# esquematico.net
KiCad netlist of a schematic drawn in Altium Designer
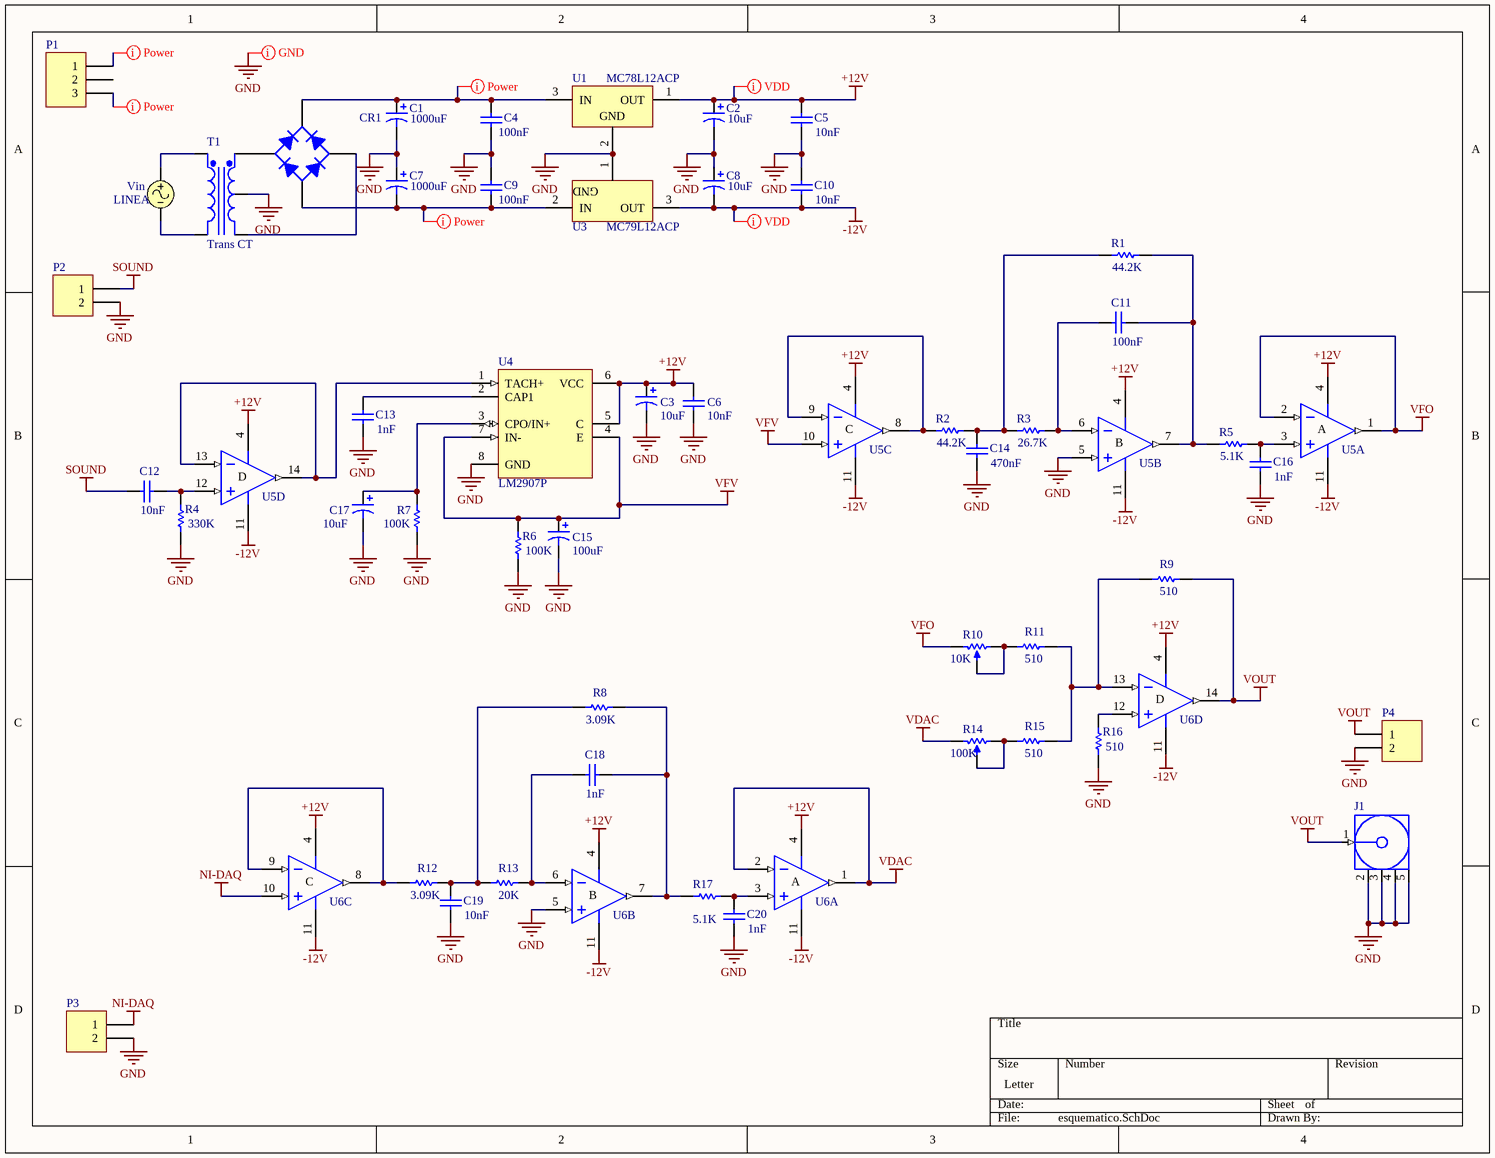
[diagram p0: esquematico.SchDoc]

(export (version "E")
  (design (tool "Eeschema 10.0.6"))
  (components
    (comp (ref "C1")
      (value "1000uF")
      (footprint "CAPPR5-10x20/H1.1")
      (description "Polarized Capacitor (Radial)")
      (fields (field (name "Comment") "Cap Pol1") (field (name "PUBLISHER") "Altium Limited"))
      (libsource (lib "Miscellaneous Devices") (part "Cap Pol1"))
    )
    (comp (ref "C2")
      (value "10uF")
      (footprint "CAPPR2-5x11")
      (description "Polarized Capacitor (Radial)")
      (fields (field (name "Comment") "Cap Pol1") (field (name "PUBLISHER") "Altium Limited"))
      (libsource (lib "Miscellaneous Devices") (part "Cap Pol1"))
    )
    (comp (ref "C3")
      (value "10uF")
      (footprint "CAPPR2-5x11")
      (description "Polarized Capacitor (Radial)")
      (fields (field (name "Comment") "Cap Pol1") (field (name "PUBLISHER") "Altium Limited"))
      (libsource (lib "Miscellaneous Devices") (part "Cap Pol1"))
    )
    (comp (ref "C4")
      (value "100nF")
      (footprint "CAPR2.54-4x2.5")
      (description "Capacitor")
      (fields (field (name "Comment") "Cap") (field (name "PUBLISHER") "Altium Limited"))
      (libsource (lib "Miscellaneous Devices") (part "Cap"))
    )
    (comp (ref "C5")
      (value "10nF")
      (footprint "CAPR2.54-4x2.5")
      (description "Capacitor")
      (fields (field (name "Comment") "Cap") (field (name "PUBLISHER") "Altium Limited"))
      (libsource (lib "Miscellaneous Devices") (part "Cap"))
    )
    (comp (ref "C6")
      (value "10nF")
      (footprint "CAPR2.54-4x2.5")
      (description "Capacitor")
      (fields (field (name "Comment") "Cap") (field (name "PUBLISHER") "Altium Limited"))
      (libsource (lib "Miscellaneous Devices") (part "Cap"))
    )
    (comp (ref "C7")
      (value "1000uF")
      (footprint "CAPPR5-10x20/H1.1")
      (description "Polarized Capacitor (Radial)")
      (fields (field (name "Comment") "Cap Pol1") (field (name "PUBLISHER") "Altium Limited"))
      (libsource (lib "Miscellaneous Devices") (part "Cap Pol1"))
    )
    (comp (ref "C8")
      (value "10uF")
      (footprint "CAPPR2-5x11")
      (description "Polarized Capacitor (Radial)")
      (fields (field (name "Comment") "Cap Pol1") (field (name "PUBLISHER") "Altium Limited"))
      (libsource (lib "Miscellaneous Devices") (part "Cap Pol1"))
    )
    (comp (ref "C9")
      (value "100nF")
      (footprint "CAPR2.54-4x2.5")
      (description "Capacitor")
      (fields (field (name "Comment") "Cap") (field (name "PUBLISHER") "Altium Limited"))
      (libsource (lib "Miscellaneous Devices") (part "Cap"))
    )
    (comp (ref "C10")
      (value "10nF")
      (footprint "CAPR2.54-4x2.5")
      (description "Capacitor")
      (fields (field (name "Comment") "Cap") (field (name "PUBLISHER") "Altium Limited"))
      (libsource (lib "Miscellaneous Devices") (part "Cap"))
    )
    (comp (ref "C11")
      (value "100nF")
      (footprint "CAPR2.54-4x2.5")
      (description "Capacitor")
      (fields (field (name "Comment") "Cap") (field (name "PUBLISHER") "Altium Limited"))
      (libsource (lib "Miscellaneous Devices") (part "Cap"))
    )
    (comp (ref "C12")
      (value "10nF")
      (footprint "CAPR2.54-4x2.5")
      (description "Capacitor")
      (fields (field (name "Comment") "Cap") (field (name "PUBLISHER") "Altium Limited"))
      (libsource (lib "Miscellaneous Devices") (part "Cap"))
    )
    (comp (ref "C13")
      (value "1nF")
      (footprint "CAPR5.08-4x2.5")
      (description "Capacitor")
      (fields (field (name "Comment") "Cap") (field (name "PUBLISHER") "Altium Limited"))
      (libsource (lib "Miscellaneous Devices") (part "Cap"))
    )
    (comp (ref "C14")
      (value "470nF")
      (footprint "CAPR5.08-4x2.5")
      (description "Capacitor")
      (fields (field (name "Comment") "Cap") (field (name "PUBLISHER") "Altium Limited"))
      (libsource (lib "Miscellaneous Devices") (part "Cap"))
    )
    (comp (ref "C15")
      (value "100uF")
      (footprint "CAPPR2.5-6.3x11")
      (description "Polarized Capacitor (Radial)")
      (fields (field (name "Comment") "Cap Pol1") (field (name "PUBLISHER") "Altium Limited"))
      (libsource (lib "Miscellaneous Devices") (part "Cap Pol1"))
    )
    (comp (ref "C16")
      (value "1nF")
      (footprint "CAPR5.08-5.1x2.5")
      (description "Capacitor")
      (fields (field (name "Comment") "Cap") (field (name "PUBLISHER") "Altium Limited"))
      (libsource (lib "Miscellaneous Devices") (part "Cap"))
    )
    (comp (ref "C17")
      (value "10uF")
      (footprint "CAPPR2-5x11")
      (description "Polarized Capacitor (Radial)")
      (fields (field (name "Comment") "Cap Pol1") (field (name "PUBLISHER") "Altium Limited"))
      (libsource (lib "Miscellaneous Devices") (part "Cap Pol1"))
    )
    (comp (ref "C18")
      (value "1nF")
      (footprint "CAPR5.08-5.1x2.5")
      (description "Capacitor")
      (fields (field (name "Comment") "Cap") (field (name "PUBLISHER") "Altium Limited"))
      (libsource (lib "Miscellaneous Devices") (part "Cap"))
    )
    (comp (ref "C19")
      (value "10nF")
      (footprint "CAPR2.54-4x2.5")
      (description "Capacitor")
      (fields (field (name "Comment") "Cap") (field (name "PUBLISHER") "Altium Limited"))
      (libsource (lib "Miscellaneous Devices") (part "Cap"))
    )
    (comp (ref "C20")
      (value "1nF")
      (footprint "CAPR5.08-5.1x2.5")
      (description "Capacitor")
      (fields (field (name "Comment") "Cap") (field (name "PUBLISHER") "Altium Limited"))
      (libsource (lib "Miscellaneous Devices") (part "Cap"))
    )
    (comp (ref "CR1")
      (value "2KBP005")
      (footprint "D-44")
      (description "2 Amp Single Phase Rectifier Bridge")
      (fields (field (name "PUBLISHER") "Altium Limited"))
      (libsource (lib "IR Rectifier - Bridge") (part "2KBP005"))
    )
    (comp (ref "J1")
      (value "COAX-F")
      (footprint "MCX5.08-H5")
      (fields (field (name "PUBLISHER") "Altium Limited"))
      (libsource (lib "Miscellaneous Connectors") (part "COAX-F"))
    )
    (comp (ref "P1")
      (value "Header 3")
      (footprint "HDR1X3")
      (description "Header, 3-Pin")
      (fields (field (name "PUBLISHER") "Altium Limited"))
      (libsource (lib "Miscellaneous Connectors") (part "Header 3"))
    )
    (comp (ref "P2")
      (value "Header 2")
      (footprint "HDR1X2")
      (description "Header, 2-Pin")
      (fields (field (name "PUBLISHER") "Altium Limited"))
      (libsource (lib "Miscellaneous Connectors") (part "Header 2"))
    )
    (comp (ref "P3")
      (value "Header 2")
      (footprint "HDR1X2")
      (description "Header, 2-Pin")
      (fields (field (name "PUBLISHER") "Altium Limited"))
      (libsource (lib "Miscellaneous Connectors") (part "Header 2"))
    )
    (comp (ref "P4")
      (value "Header 2")
      (footprint "HDR1X2")
      (description "Header, 2-Pin")
      (fields (field (name "PUBLISHER") "Altium Limited"))
      (libsource (lib "") (part "Header 2_1"))
    )
    (comp (ref "R1")
      (value "44.2K")
      (footprint "AXIAL-0.3")
      (description "Resistor")
      (fields (field (name "Comment") "Res1") (field (name "PUBLISHER") "Altium Limited"))
      (libsource (lib "Miscellaneous Devices") (part "Res1"))
    )
    (comp (ref "R2")
      (value "44.2K")
      (footprint "AXIAL-0.3")
      (description "Resistor")
      (fields (field (name "Comment") "Res1") (field (name "PUBLISHER") "Altium Limited"))
      (libsource (lib "Miscellaneous Devices") (part "Res1"))
    )
    (comp (ref "R3")
      (value "26.7K")
      (footprint "AXIAL-0.3")
      (description "Resistor")
      (fields (field (name "Comment") "Res1") (field (name "PUBLISHER") "Altium Limited"))
      (libsource (lib "Miscellaneous Devices") (part "Res1"))
    )
    (comp (ref "R4")
      (value "330K")
      (footprint "AXIAL-0.3")
      (description "Resistor")
      (fields (field (name "Comment") "Res1") (field (name "PUBLISHER") "Altium Limited"))
      (libsource (lib "Miscellaneous Devices") (part "Res1"))
    )
    (comp (ref "R5")
      (value "5.1K")
      (footprint "AXIAL-0.3")
      (description "Resistor")
      (fields (field (name "Comment") "Res1") (field (name "PUBLISHER") "Altium Limited"))
      (libsource (lib "Miscellaneous Devices") (part "Res1"))
    )
    (comp (ref "R6")
      (value "100K")
      (footprint "AXIAL-0.3")
      (description "Resistor")
      (fields (field (name "Comment") "Res1") (field (name "PUBLISHER") "Altium Limited"))
      (libsource (lib "Miscellaneous Devices") (part "Res1"))
    )
    (comp (ref "R7")
      (value "100K")
      (footprint "AXIAL-0.3")
      (description "Resistor")
      (fields (field (name "Comment") "Res1") (field (name "PUBLISHER") "Altium Limited"))
      (libsource (lib "Miscellaneous Devices") (part "Res1"))
    )
    (comp (ref "R8")
      (value "3.09K")
      (footprint "AXIAL-0.3")
      (description "Resistor")
      (fields (field (name "Comment") "Res1") (field (name "PUBLISHER") "Altium Limited"))
      (libsource (lib "Miscellaneous Devices") (part "Res1"))
    )
    (comp (ref "R9")
      (value "510")
      (footprint "AXIAL-0.3")
      (description "Resistor")
      (fields (field (name "Comment") "Res1") (field (name "PUBLISHER") "Altium Limited"))
      (libsource (lib "Miscellaneous Devices") (part "Res1"))
    )
    (comp (ref "R10")
      (value "10K")
      (footprint "3006P")
      (description "Rectangular Trimmer Potentiometer")
      (fields (field (name "Comment") "RTrimPot"))
      (libsource (lib "libreria") (part "RTrimPot"))
    )
    (comp (ref "R11")
      (value "510")
      (footprint "AXIAL-0.3")
      (description "Resistor")
      (fields (field (name "Comment") "Res1") (field (name "PUBLISHER") "Altium Limited"))
      (libsource (lib "Miscellaneous Devices") (part "Res1"))
    )
    (comp (ref "R12")
      (value "3.09K")
      (footprint "AXIAL-0.3")
      (description "Resistor")
      (fields (field (name "Comment") "Res1") (field (name "PUBLISHER") "Altium Limited"))
      (libsource (lib "Miscellaneous Devices") (part "Res1"))
    )
    (comp (ref "R13")
      (value "20K")
      (footprint "AXIAL-0.3")
      (description "Resistor")
      (fields (field (name "Comment") "Res1") (field (name "PUBLISHER") "Altium Limited"))
      (libsource (lib "Miscellaneous Devices") (part "Res1"))
    )
    (comp (ref "R14")
      (value "100K")
      (footprint "3006P")
      (description "Rectangular Trimmer Potentiometer")
      (fields (field (name "Comment") "RTrimPot"))
      (libsource (lib "libreria") (part "RTrimPot"))
    )
    (comp (ref "R15")
      (value "510")
      (footprint "AXIAL-0.3")
      (description "Resistor")
      (fields (field (name "Comment") "Res1") (field (name "PUBLISHER") "Altium Limited"))
      (libsource (lib "Miscellaneous Devices") (part "Res1"))
    )
    (comp (ref "R16")
      (value "510")
      (footprint "AXIAL-0.3")
      (description "Resistor")
      (fields (field (name "Comment") "Res1") (field (name "PUBLISHER") "Altium Limited"))
      (libsource (lib "Miscellaneous Devices") (part "Res1"))
    )
    (comp (ref "R17")
      (value "5.1K")
      (footprint "AXIAL-0.3")
      (description "Resistor")
      (fields (field (name "Comment") "Res1") (field (name "PUBLISHER") "Altium Limited"))
      (libsource (lib "Miscellaneous Devices") (part "Res1"))
    )
    (comp (ref "T1")
      (value "Trans CT")
      (footprint "TRF_5")
      (description "Center-Tapped Transformer (Coupled Inductor Model)")
      (fields (field (name "PUBLISHER") "Altium Limited"))
      (libsource (lib "Miscellaneous Devices") (part "Trans CT"))
    )
    (comp (ref "U1")
      (value "MC78L12ACP")
      (footprint "BCY-W3/W")
      (description "Three-Terminal Low Current Positive Voltage Regulator")
      (fields (field (name "PUBLISHER") "Altium Limited"))
      (libsource (lib "ON Semi Power Mgt Voltage Regulator") (part "MC78L12ACP"))
    )
    (comp (ref "U3")
      (value "MC79L12ACP")
      (footprint "BCY-W3/W")
      (description "Three-Terminal Low Current Negative Voltage Regulator")
      (fields (field (name "PUBLISHER") "Altium Limited"))
      (libsource (lib "ON Semi Power Mgt Voltage Regulator") (part "MC79L12ACP"))
    )
    (comp (ref "U4")
      (value "LM2907P")
      (footprint "P008")
      (description "Frequency-To-Voltage Converters")
      (fields (field (name "PUBLISHER") "Altium Limited"))
      (libsource (lib "TI Converter Frequency to Voltage") (part "LM2907P"))
    )
    (comp (ref "U5")
      (value "TL084CN")
      (footprint "DIP14")
      (description "General-Purpose J-FET Quad Operational Amplifier")
      (fields (field (name "PUBLISHER") "Altium Limited"))
      (libsource (lib "ST Operational Amplifier") (part "TL084CN"))
    )
    (comp (ref "U6")
      (value "TL084CN")
      (footprint "DIP14")
      (description "General-Purpose J-FET Quad Operational Amplifier")
      (fields (field (name "PUBLISHER") "Altium Limited"))
      (libsource (lib "ST Operational Amplifier") (part "TL084CN"))
    )
    (comp (ref "Vin")
      (value "LINEA")
      (description "Sinusoidal Voltage Source")
      (fields (field (name "PUBLISHER") "Altium Limited"))
      (libsource (lib "Simulation Sources") (part "VSIN"))
    )
  )
  (nets
    (net (code "1") (name "+12V") (class "Default")
      (node (ref "C2") (pin "1") (pinfunction "1_1") (pintype "passive"))
      (node (ref "C3") (pin "1") (pinfunction "1_1") (pintype "passive"))
      (node (ref "C5") (pin "1") (pinfunction "1_1") (pintype "passive"))
      (node (ref "C6") (pin "1") (pinfunction "1_1") (pintype "passive"))
      (node (ref "U1") (pin "1") (pinfunction "OUT_1") (pintype "power_in"))
      (node (ref "U4") (pin "5") (pinfunction "C_5") (pintype "passive"))
      (node (ref "U4") (pin "6") (pinfunction "VCC_6") (pintype "power_in"))
      (node (ref "U5") (pin "4") (pinfunction "V+_4") (pintype "power_in"))
      (node (ref "U6") (pin "4") (pinfunction "V+_4") (pintype "power_in"))
    )
    (net (code "2") (name "-12V") (class "Default")
      (node (ref "C10") (pin "1") (pinfunction "1_1") (pintype "passive"))
      (node (ref "C8") (pin "2") (pinfunction "2_2") (pintype "passive"))
      (node (ref "U3") (pin "3") (pinfunction "OUT_3") (pintype "power_in"))
      (node (ref "U5") (pin "11") (pinfunction "V-_11") (pintype "power_in"))
      (node (ref "U6") (pin "11") (pinfunction "V-_11") (pintype "power_in"))
    )
    (net (code "3") (name "GND") (class "Default")
      (node (ref "C1") (pin "2") (pinfunction "2_2") (pintype "passive"))
      (node (ref "C10") (pin "2") (pinfunction "2_2") (pintype "passive"))
      (node (ref "C13") (pin "1") (pinfunction "1_1") (pintype "passive"))
      (node (ref "C14") (pin "2") (pinfunction "2_2") (pintype "passive"))
      (node (ref "C15") (pin "2") (pinfunction "2_2") (pintype "passive"))
      (node (ref "C16") (pin "1") (pinfunction "1_1") (pintype "passive"))
      (node (ref "C17") (pin "2") (pinfunction "2_2") (pintype "passive"))
      (node (ref "C19") (pin "2") (pinfunction "2_2") (pintype "passive"))
      (node (ref "C2") (pin "2") (pinfunction "2_2") (pintype "passive"))
      (node (ref "C20") (pin "1") (pinfunction "1_1") (pintype "passive"))
      (node (ref "C3") (pin "2") (pinfunction "2_2") (pintype "passive"))
      (node (ref "C4") (pin "2") (pinfunction "2_2") (pintype "passive"))
      (node (ref "C5") (pin "2") (pinfunction "2_2") (pintype "passive"))
      (node (ref "C6") (pin "2") (pinfunction "2_2") (pintype "passive"))
      (node (ref "C7") (pin "1") (pinfunction "1_1") (pintype "passive"))
      (node (ref "C8") (pin "1") (pinfunction "1_1") (pintype "passive"))
      (node (ref "C9") (pin "2") (pinfunction "2_2") (pintype "passive"))
      (node (ref "J1") (pin "2") (pinfunction "GND_2") (pintype "power_in"))
      (node (ref "J1") (pin "3") (pinfunction "GND_3") (pintype "power_in"))
      (node (ref "J1") (pin "4") (pinfunction "GND_4") (pintype "power_in"))
      (node (ref "J1") (pin "5") (pinfunction "GND_5") (pintype "power_in"))
      (node (ref "P2") (pin "2") (pinfunction "2_2") (pintype "passive"))
      (node (ref "P3") (pin "2") (pinfunction "2_2") (pintype "passive"))
      (node (ref "P4") (pin "2") (pinfunction "2_2") (pintype "passive"))
      (node (ref "R16") (pin "1") (pinfunction "1_1") (pintype "passive"))
      (node (ref "R4") (pin "1") (pinfunction "1_1") (pintype "passive"))
      (node (ref "R6") (pin "1") (pinfunction "1_1") (pintype "passive"))
      (node (ref "R7") (pin "1") (pinfunction "1_1") (pintype "passive"))
      (node (ref "T1") (pin "4") (pinfunction "SecCT_4") (pintype "passive"))
      (node (ref "U1") (pin "2") (pinfunction "GND_2") (pintype "power_in"))
      (node (ref "U3") (pin "1") (pinfunction "GND_1") (pintype "power_in"))
      (node (ref "U4") (pin "8") (pinfunction "GND_8") (pintype "power_in"))
      (node (ref "U5") (pin "5") (pinfunction "IN+_5") (pintype "input"))
      (node (ref "U6") (pin "5") (pinfunction "IN+_5") (pintype "input"))
    )
    (net (code "4") (name "NI-DAQ") (class "Default")
      (node (ref "P3") (pin "1") (pinfunction "1_1") (pintype "passive"))
      (node (ref "U6") (pin "10") (pinfunction "IN+_10") (pintype "input"))
    )
    (net (code "5") (name "Net-(C14-Pad1)") (class "Default")
      (node (ref "C14") (pin "1") (pinfunction "1_1") (pintype "passive"))
      (node (ref "R1") (pin "1") (pinfunction "1_1") (pintype "passive"))
      (node (ref "R2") (pin "2") (pinfunction "2_2") (pintype "passive"))
      (node (ref "R3") (pin "1") (pinfunction "1_1") (pintype "passive"))
    )
    (net (code "6") (name "Net-(C19-Pad1)") (class "Default")
      (node (ref "C19") (pin "1") (pinfunction "1_1") (pintype "passive"))
      (node (ref "R12") (pin "2") (pinfunction "2_2") (pintype "passive"))
      (node (ref "R13") (pin "1") (pinfunction "1_1") (pintype "passive"))
      (node (ref "R8") (pin "1") (pinfunction "1_1") (pintype "passive"))
    )
    (net (code "7") (name "Net-(CR1-A)") (class "Default")
      (node (ref "C7") (pin "2") (pinfunction "2_2") (pintype "passive"))
      (node (ref "C9") (pin "1") (pinfunction "1_1") (pintype "passive"))
      (node (ref "CR1") (pin "4") (pinfunction "A_4") (pintype "passive"))
      (node (ref "U3") (pin "2") (pinfunction "IN_2") (pintype "power_in"))
    )
    (net (code "8") (name "Net-(CR1-K)") (class "Default")
      (node (ref "C1") (pin "1") (pinfunction "1_1") (pintype "passive"))
      (node (ref "C4") (pin "1") (pinfunction "1_1") (pintype "passive"))
      (node (ref "CR1") (pin "1") (pinfunction "K_1") (pintype "passive"))
      (node (ref "U1") (pin "3") (pinfunction "IN_3") (pintype "power_in"))
    )
    (net (code "9") (name "Net-(R10-Pad2)") (class "Default")
      (node (ref "R10") (pin "2") (pinfunction "2_2") (pintype "passive"))
      (node (ref "R10") (pin "3") (pinfunction "3_3") (pintype "passive"))
      (node (ref "R11") (pin "1") (pinfunction "1_1") (pintype "passive"))
    )
    (net (code "10") (name "Net-(R14-Pad2)") (class "Default")
      (node (ref "R14") (pin "2") (pinfunction "2_2") (pintype "passive"))
      (node (ref "R14") (pin "3") (pinfunction "3_3") (pintype "passive"))
      (node (ref "R15") (pin "1") (pinfunction "1_1") (pintype "passive"))
    )
    (net (code "11") (name "Net-(T1-Pri+)") (class "Default")
      (node (ref "T1") (pin "1") (pinfunction "Pri+_1") (pintype "passive"))
      (node (ref "Vin") (pin "1") (pinfunction "1_1") (pintype "passive"))
    )
    (net (code "12") (name "Net-(T1-Pri-)") (class "Default")
      (node (ref "T1") (pin "2") (pinfunction "Pri-_2") (pintype "passive"))
      (node (ref "Vin") (pin "2") (pinfunction "2_2") (pintype "passive"))
    )
    (net (code "13") (name "Net-(T1-Sec+)") (class "Default")
      (node (ref "CR1") (pin "2") (pinfunction "C_2") (pintype "passive"))
      (node (ref "T1") (pin "3") (pinfunction "Sec+_3") (pintype "passive"))
    )
    (net (code "14") (name "Net-(T1-Sec-)") (class "Default")
      (node (ref "CR1") (pin "3") (pinfunction "C_3") (pintype "passive"))
      (node (ref "T1") (pin "5") (pinfunction "Sec-_5") (pintype "passive"))
    )
    (net (code "15") (name "Net-(U4-CAP1)") (class "Default")
      (node (ref "C13") (pin "2") (pinfunction "2_2") (pintype "passive"))
      (node (ref "U4") (pin "2") (pinfunction "CAP1_2") (pintype "passive"))
    )
    (net (code "16") (name "Net-(U4-CPO{slash}IN+)") (class "Default")
      (node (ref "C17") (pin "1") (pinfunction "1_1") (pintype "passive"))
      (node (ref "R7") (pin "2") (pinfunction "2_2") (pintype "passive"))
      (node (ref "U4") (pin "3") (pinfunction "CPO/IN+_3") (pintype "bidirectional"))
    )
    (net (code "17") (name "Net-(U4-TACH+)") (class "Default")
      (node (ref "U4") (pin "1") (pinfunction "TACH+_1") (pintype "input"))
      (node (ref "U5") (pin "13") (pinfunction "IN-_13") (pintype "input"))
      (node (ref "U5") (pin "14") (pinfunction "OUT_14") (pintype "output"))
    )
    (net (code "18") (name "Net-(U5A-IN+)") (class "Default")
      (node (ref "C16") (pin "2") (pinfunction "2_2") (pintype "passive"))
      (node (ref "R5") (pin "2") (pinfunction "2_2") (pintype "passive"))
      (node (ref "U5") (pin "3") (pinfunction "IN+_3") (pintype "input"))
    )
    (net (code "19") (name "Net-(U5B-IN-)") (class "Default")
      (node (ref "C11") (pin "2") (pinfunction "2_2") (pintype "passive"))
      (node (ref "R3") (pin "2") (pinfunction "2_2") (pintype "passive"))
      (node (ref "U5") (pin "6") (pinfunction "IN-_6") (pintype "input"))
    )
    (net (code "20") (name "Net-(U5B-OUT)") (class "Default")
      (node (ref "C11") (pin "1") (pinfunction "1_1") (pintype "passive"))
      (node (ref "R1") (pin "2") (pinfunction "2_2") (pintype "passive"))
      (node (ref "R5") (pin "1") (pinfunction "1_1") (pintype "passive"))
      (node (ref "U5") (pin "7") (pinfunction "OUT_7") (pintype "output"))
    )
    (net (code "21") (name "Net-(U5C-IN-)") (class "Default")
      (node (ref "R2") (pin "1") (pinfunction "1_1") (pintype "passive"))
      (node (ref "U5") (pin "8") (pinfunction "OUT_8") (pintype "output"))
      (node (ref "U5") (pin "9") (pinfunction "IN-_9") (pintype "input"))
    )
    (net (code "22") (name "Net-(U5D-IN+)") (class "Default")
      (node (ref "C12") (pin "1") (pinfunction "1_1") (pintype "passive"))
      (node (ref "R4") (pin "2") (pinfunction "2_2") (pintype "passive"))
      (node (ref "U5") (pin "12") (pinfunction "IN+_12") (pintype "input"))
    )
    (net (code "23") (name "Net-(U6A-IN+)") (class "Default")
      (node (ref "C20") (pin "2") (pinfunction "2_2") (pintype "passive"))
      (node (ref "R17") (pin "2") (pinfunction "2_2") (pintype "passive"))
      (node (ref "U6") (pin "3") (pinfunction "IN+_3") (pintype "input"))
    )
    (net (code "24") (name "Net-(U6B-IN-)") (class "Default")
      (node (ref "C18") (pin "2") (pinfunction "2_2") (pintype "passive"))
      (node (ref "R13") (pin "2") (pinfunction "2_2") (pintype "passive"))
      (node (ref "U6") (pin "6") (pinfunction "IN-_6") (pintype "input"))
    )
    (net (code "25") (name "Net-(U6B-OUT)") (class "Default")
      (node (ref "C18") (pin "1") (pinfunction "1_1") (pintype "passive"))
      (node (ref "R17") (pin "1") (pinfunction "1_1") (pintype "passive"))
      (node (ref "R8") (pin "2") (pinfunction "2_2") (pintype "passive"))
      (node (ref "U6") (pin "7") (pinfunction "OUT_7") (pintype "output"))
    )
    (net (code "26") (name "Net-(U6C-IN-)") (class "Default")
      (node (ref "R12") (pin "1") (pinfunction "1_1") (pintype "passive"))
      (node (ref "U6") (pin "8") (pinfunction "OUT_8") (pintype "output"))
      (node (ref "U6") (pin "9") (pinfunction "IN-_9") (pintype "input"))
    )
    (net (code "27") (name "Net-(U6D-IN+)") (class "Default")
      (node (ref "R16") (pin "2") (pinfunction "2_2") (pintype "passive"))
      (node (ref "U6") (pin "12") (pinfunction "IN+_12") (pintype "input"))
    )
    (net (code "28") (name "Net-(U6D-IN-)") (class "Default")
      (node (ref "R11") (pin "2") (pinfunction "2_2") (pintype "passive"))
      (node (ref "R15") (pin "2") (pinfunction "2_2") (pintype "passive"))
      (node (ref "R9") (pin "1") (pinfunction "1_1") (pintype "passive"))
      (node (ref "U6") (pin "13") (pinfunction "IN-_13") (pintype "input"))
    )
    (net (code "29") (name "SOUND") (class "Default")
      (node (ref "C12") (pin "2") (pinfunction "2_2") (pintype "passive"))
      (node (ref "P2") (pin "1") (pinfunction "1_1") (pintype "passive"))
    )
    (net (code "30") (name "VDAC") (class "Default")
      (node (ref "R14") (pin "1") (pinfunction "1_1") (pintype "passive"))
      (node (ref "U6") (pin "1") (pinfunction "OUT_1") (pintype "output"))
      (node (ref "U6") (pin "2") (pinfunction "IN-_2") (pintype "input"))
    )
    (net (code "31") (name "VFO") (class "Default")
      (node (ref "R10") (pin "1") (pinfunction "1_1") (pintype "passive"))
      (node (ref "U5") (pin "1") (pinfunction "OUT_1") (pintype "output"))
      (node (ref "U5") (pin "2") (pinfunction "IN-_2") (pintype "input"))
    )
    (net (code "32") (name "VFV") (class "Default")
      (node (ref "C15") (pin "1") (pinfunction "1_1") (pintype "passive"))
      (node (ref "R6") (pin "2") (pinfunction "2_2") (pintype "passive"))
      (node (ref "U4") (pin "4") (pinfunction "E_4") (pintype "passive"))
      (node (ref "U4") (pin "7") (pinfunction "IN-_7") (pintype "input"))
      (node (ref "U5") (pin "10") (pinfunction "IN+_10") (pintype "input"))
    )
    (net (code "33") (name "VOUT") (class "Default")
      (node (ref "J1") (pin "1") (pinfunction "Signal_1") (pintype "input"))
      (node (ref "P4") (pin "1") (pinfunction "1_1") (pintype "passive"))
      (node (ref "R9") (pin "2") (pinfunction "2_2") (pintype "passive"))
      (node (ref "U6") (pin "14") (pinfunction "OUT_14") (pintype "output"))
    )
    (net (code "34") (name "unconnected-(P1-Pad1)") (class "Default")
      (node (ref "P1") (pin "1") (pinfunction "1_1") (pintype "passive"))
    )
    (net (code "35") (name "unconnected-(P1-Pad2)") (class "Default")
      (node (ref "P1") (pin "2") (pinfunction "2_2") (pintype "passive"))
    )
    (net (code "36") (name "unconnected-(P1-Pad3)") (class "Default")
      (node (ref "P1") (pin "3") (pinfunction "3_3") (pintype "passive"))
    )
  )
)
